# OLED_64x32_V3.net
KiCad netlist of a schematic drawn in EAGLE
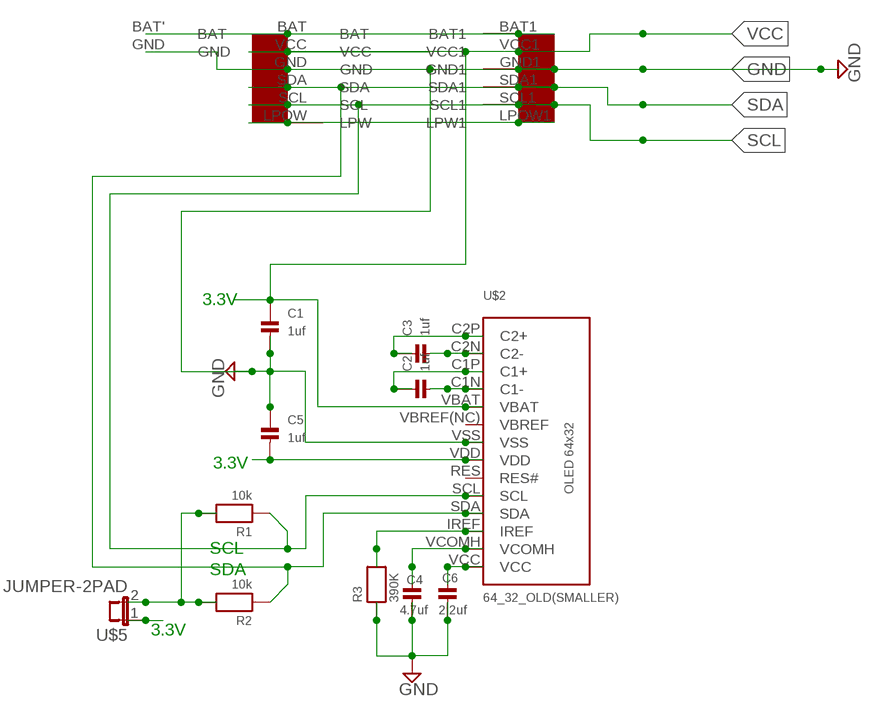
[diagram p0: schematic, sheet 1]

(export (version "E")
  (design (tool "Eeschema 10.0.6"))
  (components
    (comp (ref "C1")
      (value "1uf")
      (footprint "eagle-import:0603")
      (libsource (lib "eagle-import") (part "CAP_CERAMIC0603"))
    )
    (comp (ref "C2")
      (value "1uf")
      (footprint "eagle-import:0603")
      (libsource (lib "eagle-import") (part "CAP_CERAMIC0603"))
    )
    (comp (ref "C3")
      (value "1uf")
      (footprint "eagle-import:0603")
      (libsource (lib "eagle-import") (part "CAP_CERAMIC0603"))
    )
    (comp (ref "C4")
      (value "4.7uf")
      (footprint "eagle-import:0603")
      (libsource (lib "eagle-import") (part "CAP_CERAMIC0603"))
    )
    (comp (ref "C5")
      (value "1uf")
      (footprint "eagle-import:0603")
      (libsource (lib "eagle-import") (part "CAP_CERAMIC0603"))
    )
    (comp (ref "C6")
      (value "2.2uf")
      (footprint "eagle-import:0603")
      (libsource (lib "eagle-import") (part "CAP_CERAMIC0603"))
    )
    (comp (ref "R1")
      (value "10k")
      (footprint "eagle-import:0603")
      (libsource (lib "eagle-import") (part "RESISTOR0603"))
    )
    (comp (ref "R2")
      (value "10k")
      (footprint "eagle-import:0603")
      (libsource (lib "eagle-import") (part "RESISTOR0603"))
    )
    (comp (ref "R3")
      (value "390K")
      (footprint "eagle-import:0603")
      (libsource (lib "eagle-import") (part "RESISTOR0603"))
    )
    (comp (ref "U$1")
      (value "EZ-I2CHEADERV1")
      (footprint "eagle-import:EZ-I2CHEADERV1")
      (libsource (lib "eagle-import") (part "EZ-I2CHEADERV1"))
    )
    (comp (ref "U$2")
      (value "64_32_OLD(SMALLER)")
      (footprint "eagle-import:62_32_OLED(SMALLER)")
      (libsource (lib "eagle-import") (part "64_32_OLD(SMALLER)"))
    )
    (comp (ref "U$4")
      (value "MINI_BATTERY_HOLES")
      (footprint "eagle-import:MINI_BATTERY_HOLES")
      (libsource (lib "eagle-import") (part "MINI_BATTERY_HOLES"))
    )
    (comp (ref "U$5")
      (value "JUMPER-2PAD")
      (footprint "eagle-import:JUMPER-2PAD")
      (libsource (lib "eagle-import") (part "JUMPER-2PAD"))
    )
  )
  (nets
    (net (code "1") (name "GND") (class "Default")
      (node (ref "C1") (pin "2") (pinfunction "P$2_2") (pintype "passive"))
      (node (ref "C4") (pin "2") (pinfunction "P$2_2") (pintype "passive"))
      (node (ref "C5") (pin "1") (pinfunction "P$1_1") (pintype "passive"))
      (node (ref "C6") (pin "2") (pinfunction "P$2_2") (pintype "passive"))
      (node (ref "R3") (pin "1") (pinfunction "1_1") (pintype "passive"))
      (node (ref "U$1") (pin "GND") (pinfunction "GND_GND") (pintype "bidirectional"))
      (node (ref "U$1") (pin "GND1") (pinfunction "GND1_GND1") (pintype "bidirectional"))
      (node (ref "U$2") (pin "VSS") (pinfunction "VSS_VSS") (pintype "bidirectional"))
      (node (ref "U$4") (pin "GND") (pinfunction "GND_GND") (pintype "bidirectional"))
    )
    (net (code "2") (name "Net-(C2-P$1)") (class "Default")
      (node (ref "C2") (pin "1") (pinfunction "P$1_1") (pintype "passive"))
      (node (ref "U$2") (pin "C1P") (pinfunction "C1+_C1P") (pintype "bidirectional"))
    )
    (net (code "3") (name "Net-(C2-P$2)") (class "Default")
      (node (ref "C2") (pin "2") (pinfunction "P$2_2") (pintype "passive"))
      (node (ref "U$2") (pin "C1N") (pinfunction "C1-_C1N") (pintype "bidirectional"))
    )
    (net (code "4") (name "Net-(C3-P$1)") (class "Default")
      (node (ref "C3") (pin "1") (pinfunction "P$1_1") (pintype "passive"))
      (node (ref "U$2") (pin "C2P") (pinfunction "C2+_C2P") (pintype "bidirectional"))
    )
    (net (code "5") (name "Net-(C3-P$2)") (class "Default")
      (node (ref "C3") (pin "2") (pinfunction "P$2_2") (pintype "passive"))
      (node (ref "U$2") (pin "C2N") (pinfunction "C2-_C2N") (pintype "bidirectional"))
    )
    (net (code "6") (name "Net-(C4-P$1)") (class "Default")
      (node (ref "C4") (pin "1") (pinfunction "P$1_1") (pintype "passive"))
      (node (ref "U$2") (pin "VCOMH") (pinfunction "VCOMH_VCOMH") (pintype "bidirectional"))
    )
    (net (code "7") (name "Net-(C6-P$1)") (class "Default")
      (node (ref "C6") (pin "1") (pinfunction "P$1_1") (pintype "passive"))
      (node (ref "U$2") (pin "VCC") (pinfunction "VCC_VCC") (pintype "bidirectional"))
    )
    (net (code "8") (name "Net-(R1-Pad2)") (class "Default")
      (node (ref "R1") (pin "2") (pinfunction "2_2") (pintype "passive"))
      (node (ref "R2") (pin "2") (pinfunction "2_2") (pintype "passive"))
      (node (ref "U$5") (pin "2") (pinfunction "2_2") (pintype "passive"))
    )
    (net (code "9") (name "Net-(R3-Pad2)") (class "Default")
      (node (ref "R3") (pin "2") (pinfunction "2_2") (pintype "passive"))
      (node (ref "U$2") (pin "IREF") (pinfunction "IREF_IREF") (pintype "bidirectional"))
    )
    (net (code "10") (name "Net-(U$1-LPW)") (class "Default")
      (node (ref "U$1") (pin "LPOW") (pinfunction "LPW_LPOW") (pintype "bidirectional"))
      (node (ref "U$1") (pin "LPOW1") (pinfunction "LPW1_LPOW1") (pintype "bidirectional"))
    )
    (net (code "11") (name "Net-(U$4-BAT)") (class "Default")
      (node (ref "U$1") (pin "BAT") (pinfunction "BAT_BAT") (pintype "bidirectional"))
      (node (ref "U$1") (pin "BAT1") (pinfunction "BAT1_BAT1") (pintype "bidirectional"))
      (node (ref "U$4") (pin "BAT'") (pinfunction "BAT_BAT'") (pintype "bidirectional"))
    )
    (net (code "12") (name "SCL") (class "Default")
      (node (ref "R1") (pin "1") (pinfunction "1_1") (pintype "passive"))
      (node (ref "U$1") (pin "SCL") (pinfunction "SCL_SCL") (pintype "bidirectional"))
      (node (ref "U$1") (pin "SCL1") (pinfunction "SCL1_SCL1") (pintype "bidirectional"))
      (node (ref "U$2") (pin "SCL") (pinfunction "SCL_SCL") (pintype "bidirectional"))
    )
    (net (code "13") (name "SDA") (class "Default")
      (node (ref "R2") (pin "1") (pinfunction "1_1") (pintype "passive"))
      (node (ref "U$1") (pin "SDA") (pinfunction "SDA_SDA") (pintype "bidirectional"))
      (node (ref "U$1") (pin "SDA1") (pinfunction "SDA1_SDA1") (pintype "bidirectional"))
      (node (ref "U$2") (pin "SDA") (pinfunction "SDA_SDA") (pintype "bidirectional"))
    )
    (net (code "14") (name "VCC") (class "Default")
      (node (ref "C1") (pin "1") (pinfunction "P$1_1") (pintype "passive"))
      (node (ref "C5") (pin "2") (pinfunction "P$2_2") (pintype "passive"))
      (node (ref "U$1") (pin "VCC") (pinfunction "VCC_VCC") (pintype "bidirectional"))
      (node (ref "U$1") (pin "VCC1") (pinfunction "VCC1_VCC1") (pintype "bidirectional"))
      (node (ref "U$2") (pin "VBAT") (pinfunction "VBAT_VBAT") (pintype "bidirectional"))
      (node (ref "U$2") (pin "VDD") (pinfunction "VDD_VDD") (pintype "bidirectional"))
      (node (ref "U$5") (pin "1") (pinfunction "1_1") (pintype "passive"))
    )
    (net (code "15") (name "unconnected-(U$2-RES#-PadRES)") (class "Default")
      (node (ref "U$2") (pin "RES") (pinfunction "RES#_RES") (pintype "bidirectional"))
    )
    (net (code "16") (name "unconnected-(U$2-VBREF-PadVBREF(NC))") (class "Default")
      (node (ref "U$2") (pin "VBREF(NC)") (pinfunction "VBREF_VBREF(NC)") (pintype "bidirectional"))
    )
  )
)
